# toplevel.net
KiCad netlist of a schematic drawn in Altium Designer
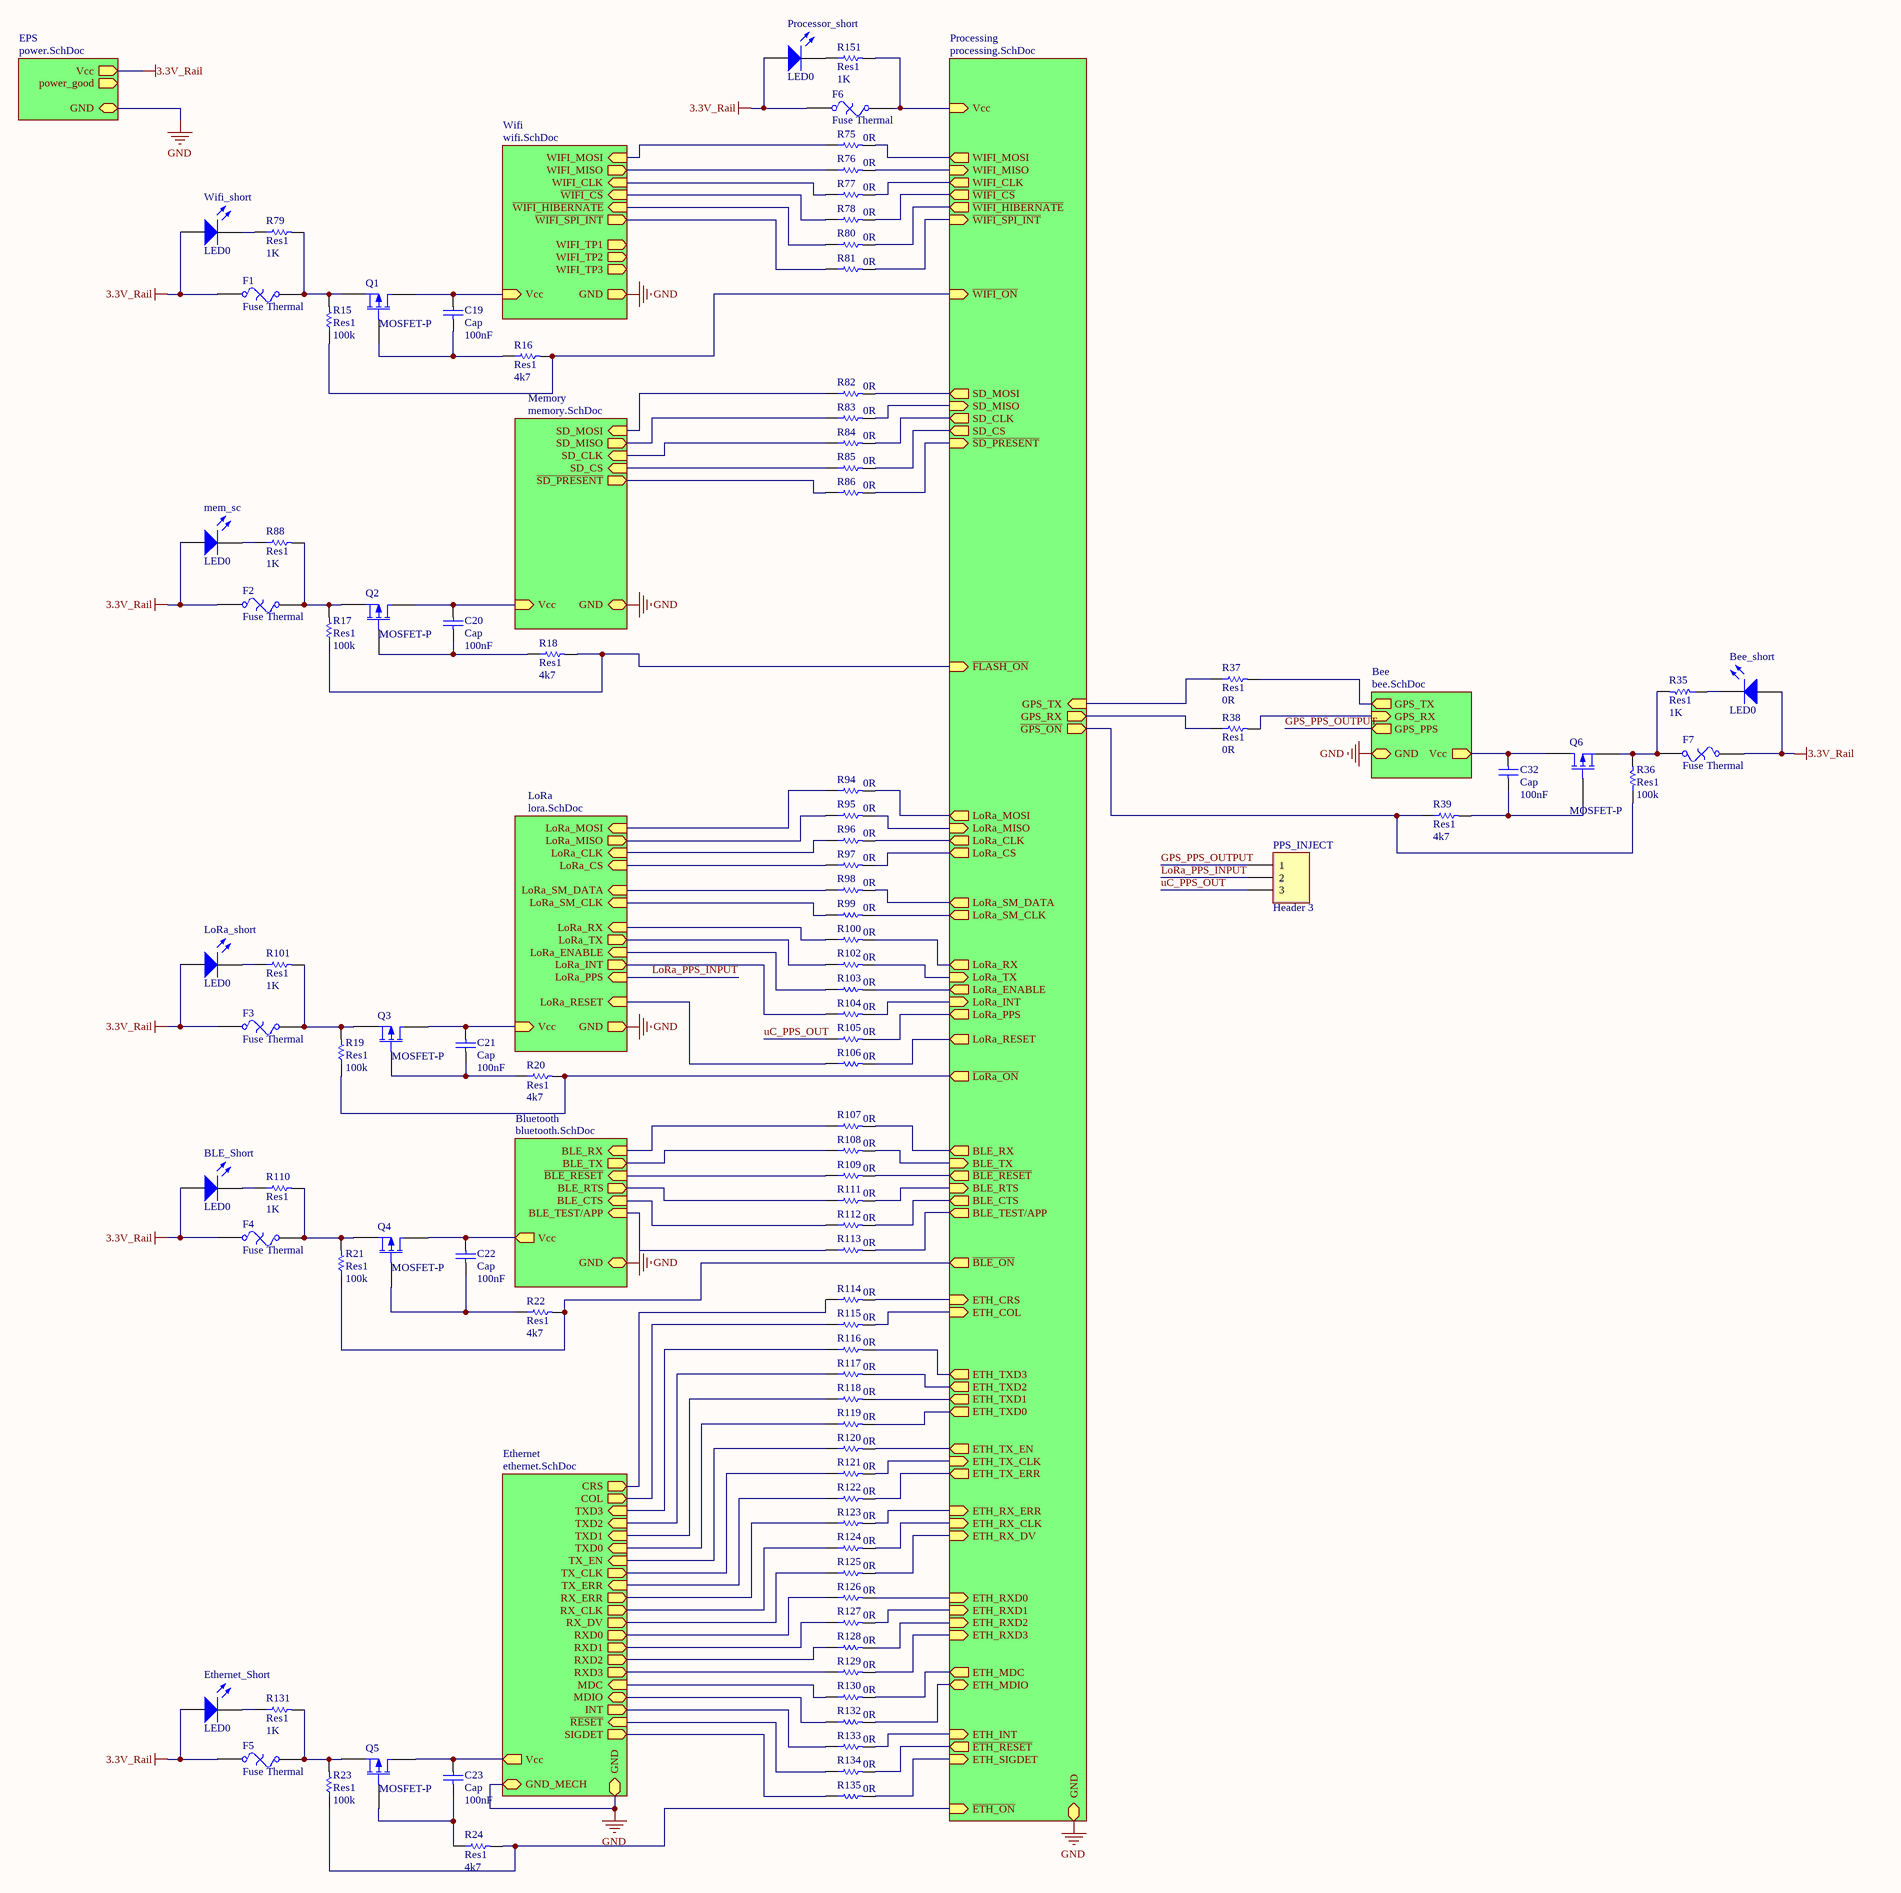
[diagram p0: toplevel.SchDoc]

(export (version "E")
  (design (tool "Eeschema 10.0.6"))
  (components
    (comp (ref "Bee_short")
      (value "LED0")
      (footprint "C0603")
      (description "Typical INFRARED GaAs LED")
      (fields (field (name "PUBLISHER") "Altium Limited"))
      (libsource (lib "any") (part "LED0"))
    )
    (comp (ref "BLE_Short")
      (value "LED0")
      (footprint "C0603")
      (description "Typical INFRARED GaAs LED")
      (fields (field (name "PUBLISHER") "Altium Limited"))
      (libsource (lib "any") (part "LED0"))
    )
    (comp (ref "C19")
      (value "Cap")
      (footprint "6-0805_L")
      (description "Capacitor")
      (fields (field (name "ALTIUM_VALUE") "100nF") (field (name "PUBLISHER") "Altium Limited"))
      (libsource (lib "Miscellaneous Devices") (part "Cap"))
    )
    (comp (ref "C20")
      (value "Cap")
      (footprint "6-0805_L")
      (description "Capacitor")
      (fields (field (name "ALTIUM_VALUE") "100nF") (field (name "PUBLISHER") "Altium Limited"))
      (libsource (lib "Miscellaneous Devices") (part "Cap"))
    )
    (comp (ref "C21")
      (value "Cap")
      (footprint "6-0805_L")
      (description "Capacitor")
      (fields (field (name "ALTIUM_VALUE") "100nF") (field (name "PUBLISHER") "Altium Limited"))
      (libsource (lib "Miscellaneous Devices") (part "Cap"))
    )
    (comp (ref "C22")
      (value "Cap")
      (footprint "6-0805_L")
      (description "Capacitor")
      (fields (field (name "ALTIUM_VALUE") "100nF") (field (name "PUBLISHER") "Altium Limited"))
      (libsource (lib "Miscellaneous Devices") (part "Cap"))
    )
    (comp (ref "C23")
      (value "Cap")
      (footprint "6-0805_L")
      (description "Capacitor")
      (fields (field (name "ALTIUM_VALUE") "100nF") (field (name "PUBLISHER") "Altium Limited"))
      (libsource (lib "Miscellaneous Devices") (part "Cap"))
    )
    (comp (ref "C32")
      (value "Cap")
      (footprint "6-0805_L")
      (description "Capacitor")
      (fields (field (name "ALTIUM_VALUE") "100nF") (field (name "PUBLISHER") "Altium Limited"))
      (libsource (lib "Miscellaneous Devices") (part "Cap"))
    )
    (comp (ref "Ethernet_Short")
      (value "LED0")
      (footprint "C0603")
      (description "Typical INFRARED GaAs LED")
      (fields (field (name "PUBLISHER") "Altium Limited"))
      (libsource (lib "any") (part "LED0"))
    )
    (comp (ref "F1")
      (value "Fuse Thermal")
      (footprint "1812-polyfuse")
      (description "Thermal Fuse")
      (fields (field (name "PUBLISHER") "Altium Limited"))
      (libsource (lib "Any") (part "Fuse Thermal"))
    )
    (comp (ref "F2")
      (value "Fuse Thermal")
      (footprint "1812-polyfuse")
      (description "Thermal Fuse")
      (fields (field (name "PUBLISHER") "Altium Limited"))
      (libsource (lib "Any") (part "Fuse Thermal"))
    )
    (comp (ref "F3")
      (value "Fuse Thermal")
      (footprint "1812-polyfuse")
      (description "Thermal Fuse")
      (fields (field (name "PUBLISHER") "Altium Limited"))
      (libsource (lib "Any") (part "Fuse Thermal"))
    )
    (comp (ref "F4")
      (value "Fuse Thermal")
      (footprint "1812-polyfuse")
      (description "Thermal Fuse")
      (fields (field (name "PUBLISHER") "Altium Limited"))
      (libsource (lib "Any") (part "Fuse Thermal"))
    )
    (comp (ref "F5")
      (value "Fuse Thermal")
      (footprint "1812-polyfuse")
      (description "Thermal Fuse")
      (fields (field (name "PUBLISHER") "Altium Limited"))
      (libsource (lib "Any") (part "Fuse Thermal"))
    )
    (comp (ref "F6")
      (value "Fuse Thermal")
      (footprint "1812-polyfuse")
      (description "Thermal Fuse")
      (fields (field (name "PUBLISHER") "Altium Limited"))
      (libsource (lib "Any") (part "Fuse Thermal"))
    )
    (comp (ref "F7")
      (value "Fuse Thermal")
      (footprint "1812-polyfuse")
      (description "Thermal Fuse")
      (fields (field (name "PUBLISHER") "Altium Limited"))
      (libsource (lib "") (part "Fuse Thermal_1"))
    )
    (comp (ref "LoRa_short")
      (value "LED0")
      (footprint "C0603")
      (description "Typical INFRARED GaAs LED")
      (fields (field (name "PUBLISHER") "Altium Limited"))
      (libsource (lib "any") (part "LED0"))
    )
    (comp (ref "mem_sc")
      (value "LED0")
      (footprint "C0603")
      (description "Typical INFRARED GaAs LED")
      (fields (field (name "PUBLISHER") "Altium Limited"))
      (libsource (lib "any") (part "LED0"))
    )
    (comp (ref "PPS_INJECT")
      (value "Header 3")
      (footprint "HDR1X3")
      (description "Header, 3-Pin")
      (fields (field (name "PUBLISHER") "Altium Limited"))
      (libsource (lib "Miscellaneous Connectors") (part "Header 3"))
    )
    (comp (ref "Processor_short")
      (value "LED0")
      (footprint "C0603")
      (description "Typical INFRARED GaAs LED")
      (fields (field (name "PUBLISHER") "Altium Limited"))
      (libsource (lib "any") (part "LED0"))
    )
    (comp (ref "Q1")
      (value "MOSFET-P")
      (footprint "SOT23_N")
      (description "P-Channel MOSFET")
      (fields (field (name "PUBLISHER") "Altium Limited"))
      (libsource (lib "Miscellaneous Devices") (part "MOSFET-P"))
    )
    (comp (ref "Q2")
      (value "MOSFET-P")
      (footprint "SOT23_N")
      (description "P-Channel MOSFET")
      (fields (field (name "PUBLISHER") "Altium Limited"))
      (libsource (lib "Miscellaneous Devices") (part "MOSFET-P"))
    )
    (comp (ref "Q3")
      (value "MOSFET-P")
      (footprint "SOT23_N")
      (description "P-Channel MOSFET")
      (fields (field (name "PUBLISHER") "Altium Limited"))
      (libsource (lib "Miscellaneous Devices") (part "MOSFET-P"))
    )
    (comp (ref "Q4")
      (value "MOSFET-P")
      (footprint "SOT23_N")
      (description "P-Channel MOSFET")
      (fields (field (name "PUBLISHER") "Altium Limited"))
      (libsource (lib "Miscellaneous Devices") (part "MOSFET-P"))
    )
    (comp (ref "Q5")
      (value "MOSFET-P")
      (footprint "SOT23_N")
      (description "P-Channel MOSFET")
      (fields (field (name "PUBLISHER") "Altium Limited"))
      (libsource (lib "Miscellaneous Devices") (part "MOSFET-P"))
    )
    (comp (ref "Q6")
      (value "MOSFET-P")
      (footprint "SOT23_N")
      (description "P-Channel MOSFET")
      (fields (field (name "PUBLISHER") "Altium Limited"))
      (libsource (lib "Miscellaneous Devices") (part "MOSFET-P"))
    )
    (comp (ref "R15")
      (value "Res1")
      (footprint "R0603")
      (description "Resistor")
      (fields (field (name "ALTIUM_VALUE") "100k") (field (name "PUBLISHER") "Altium Limited"))
      (libsource (lib "Miscellaneous Devices") (part "Res1"))
    )
    (comp (ref "R16")
      (value "Res1")
      (footprint "R0603")
      (description "Resistor")
      (fields (field (name "ALTIUM_VALUE") "4k7") (field (name "PUBLISHER") "Altium Limited"))
      (libsource (lib "Miscellaneous Devices") (part "Res1"))
    )
    (comp (ref "R17")
      (value "Res1")
      (footprint "R0603")
      (description "Resistor")
      (fields (field (name "ALTIUM_VALUE") "100k") (field (name "PUBLISHER") "Altium Limited"))
      (libsource (lib "Miscellaneous Devices") (part "Res1"))
    )
    (comp (ref "R18")
      (value "Res1")
      (footprint "R0603")
      (description "Resistor")
      (fields (field (name "ALTIUM_VALUE") "4k7") (field (name "PUBLISHER") "Altium Limited"))
      (libsource (lib "Miscellaneous Devices") (part "Res1"))
    )
    (comp (ref "R19")
      (value "Res1")
      (footprint "R0603")
      (description "Resistor")
      (fields (field (name "ALTIUM_VALUE") "100k") (field (name "PUBLISHER") "Altium Limited"))
      (libsource (lib "Miscellaneous Devices") (part "Res1"))
    )
    (comp (ref "R20")
      (value "Res1")
      (footprint "R0603")
      (description "Resistor")
      (fields (field (name "ALTIUM_VALUE") "4k7") (field (name "PUBLISHER") "Altium Limited"))
      (libsource (lib "Miscellaneous Devices") (part "Res1"))
    )
    (comp (ref "R21")
      (value "Res1")
      (footprint "R0603")
      (description "Resistor")
      (fields (field (name "ALTIUM_VALUE") "100k") (field (name "PUBLISHER") "Altium Limited"))
      (libsource (lib "Miscellaneous Devices") (part "Res1"))
    )
    (comp (ref "R22")
      (value "Res1")
      (footprint "R0603")
      (description "Resistor")
      (fields (field (name "ALTIUM_VALUE") "4k7") (field (name "PUBLISHER") "Altium Limited"))
      (libsource (lib "Miscellaneous Devices") (part "Res1"))
    )
    (comp (ref "R23")
      (value "Res1")
      (footprint "R0603")
      (description "Resistor")
      (fields (field (name "ALTIUM_VALUE") "100k") (field (name "PUBLISHER") "Altium Limited"))
      (libsource (lib "Miscellaneous Devices") (part "Res1"))
    )
    (comp (ref "R24")
      (value "Res1")
      (footprint "R0603")
      (description "Resistor")
      (fields (field (name "ALTIUM_VALUE") "4k7") (field (name "PUBLISHER") "Altium Limited"))
      (libsource (lib "Miscellaneous Devices") (part "Res1"))
    )
    (comp (ref "R35")
      (value "Res1")
      (footprint "R0603")
      (description "Resistor")
      (fields (field (name "ALTIUM_VALUE") "1K") (field (name "PUBLISHER") "Altium Limited"))
      (libsource (lib "any") (part "Res1"))
    )
    (comp (ref "R36")
      (value "Res1")
      (footprint "R0603")
      (description "Resistor")
      (fields (field (name "ALTIUM_VALUE") "100k") (field (name "PUBLISHER") "Altium Limited"))
      (libsource (lib "Miscellaneous Devices") (part "Res1"))
    )
    (comp (ref "R37")
      (value "Res1")
      (footprint "R0603")
      (description "Resistor")
      (fields (field (name "ALTIUM_VALUE") "0R") (field (name "PUBLISHER") "Altium Limited"))
      (libsource (lib "Miscellaneous Devices") (part "Res1"))
    )
    (comp (ref "R38")
      (value "Res1")
      (footprint "R0603")
      (description "Resistor")
      (fields (field (name "ALTIUM_VALUE") "0R") (field (name "PUBLISHER") "Altium Limited"))
      (libsource (lib "Miscellaneous Devices") (part "Res1"))
    )
    (comp (ref "R39")
      (value "Res1")
      (footprint "R0603")
      (description "Resistor")
      (fields (field (name "ALTIUM_VALUE") "4k7") (field (name "PUBLISHER") "Altium Limited"))
      (libsource (lib "Miscellaneous Devices") (part "Res1"))
    )
    (comp (ref "R75")
      (value "0R")
      (footprint "R0603")
      (description "Resistor")
      (fields (field (name "PUBLISHER") "Altium Limited"))
      (libsource (lib "any") (part "Res1"))
    )
    (comp (ref "R76")
      (value "0R")
      (footprint "R0603")
      (description "Resistor")
      (fields (field (name "PUBLISHER") "Altium Limited"))
      (libsource (lib "any") (part "Res1"))
    )
    (comp (ref "R77")
      (value "0R")
      (footprint "R0603")
      (description "Resistor")
      (fields (field (name "PUBLISHER") "Altium Limited"))
      (libsource (lib "any") (part "Res1"))
    )
    (comp (ref "R78")
      (value "0R")
      (footprint "R0603")
      (description "Resistor")
      (fields (field (name "PUBLISHER") "Altium Limited"))
      (libsource (lib "any") (part "Res1"))
    )
    (comp (ref "R79")
      (value "Res1")
      (footprint "R0603")
      (description "Resistor")
      (fields (field (name "ALTIUM_VALUE") "1K") (field (name "PUBLISHER") "Altium Limited"))
      (libsource (lib "any") (part "Res1"))
    )
    (comp (ref "R80")
      (value "0R")
      (footprint "R0603")
      (description "Resistor")
      (fields (field (name "PUBLISHER") "Altium Limited"))
      (libsource (lib "any") (part "Res1"))
    )
    (comp (ref "R81")
      (value "0R")
      (footprint "R0603")
      (description "Resistor")
      (fields (field (name "PUBLISHER") "Altium Limited"))
      (libsource (lib "any") (part "Res1"))
    )
    (comp (ref "R82")
      (value "0R")
      (footprint "R0603")
      (description "Resistor")
      (fields (field (name "PUBLISHER") "Altium Limited"))
      (libsource (lib "any") (part "Res1"))
    )
    (comp (ref "R83")
      (value "0R")
      (footprint "R0603")
      (description "Resistor")
      (fields (field (name "PUBLISHER") "Altium Limited"))
      (libsource (lib "any") (part "Res1"))
    )
    (comp (ref "R84")
      (value "0R")
      (footprint "R0603")
      (description "Resistor")
      (fields (field (name "PUBLISHER") "Altium Limited"))
      (libsource (lib "any") (part "Res1"))
    )
    (comp (ref "R85")
      (value "0R")
      (footprint "R0603")
      (description "Resistor")
      (fields (field (name "PUBLISHER") "Altium Limited"))
      (libsource (lib "any") (part "Res1"))
    )
    (comp (ref "R86")
      (value "0R")
      (footprint "R0603")
      (description "Resistor")
      (fields (field (name "PUBLISHER") "Altium Limited"))
      (libsource (lib "any") (part "Res1"))
    )
    (comp (ref "R88")
      (value "Res1")
      (footprint "R0603")
      (description "Resistor")
      (fields (field (name "ALTIUM_VALUE") "1K") (field (name "PUBLISHER") "Altium Limited"))
      (libsource (lib "any") (part "Res1"))
    )
    (comp (ref "R94")
      (value "0R")
      (footprint "R0603")
      (description "Resistor")
      (fields (field (name "PUBLISHER") "Altium Limited"))
      (libsource (lib "any") (part "Res1"))
    )
    (comp (ref "R95")
      (value "0R")
      (footprint "R0603")
      (description "Resistor")
      (fields (field (name "PUBLISHER") "Altium Limited"))
      (libsource (lib "any") (part "Res1"))
    )
    (comp (ref "R96")
      (value "0R")
      (footprint "R0603")
      (description "Resistor")
      (fields (field (name "PUBLISHER") "Altium Limited"))
      (libsource (lib "any") (part "Res1"))
    )
    (comp (ref "R97")
      (value "0R")
      (footprint "R0603")
      (description "Resistor")
      (fields (field (name "PUBLISHER") "Altium Limited"))
      (libsource (lib "any") (part "Res1"))
    )
    (comp (ref "R98")
      (value "0R")
      (footprint "R0603")
      (description "Resistor")
      (fields (field (name "PUBLISHER") "Altium Limited"))
      (libsource (lib "any") (part "Res1"))
    )
    (comp (ref "R99")
      (value "0R")
      (footprint "R0603")
      (description "Resistor")
      (fields (field (name "PUBLISHER") "Altium Limited"))
      (libsource (lib "any") (part "Res1"))
    )
    (comp (ref "R100")
      (value "0R")
      (footprint "R0603")
      (description "Resistor")
      (fields (field (name "PUBLISHER") "Altium Limited"))
      (libsource (lib "any") (part "Res1"))
    )
    (comp (ref "R101")
      (value "Res1")
      (footprint "R0603")
      (description "Resistor")
      (fields (field (name "ALTIUM_VALUE") "1K") (field (name "PUBLISHER") "Altium Limited"))
      (libsource (lib "any") (part "Res1"))
    )
    (comp (ref "R102")
      (value "0R")
      (footprint "R0603")
      (description "Resistor")
      (fields (field (name "PUBLISHER") "Altium Limited"))
      (libsource (lib "any") (part "Res1"))
    )
    (comp (ref "R103")
      (value "0R")
      (footprint "R0603")
      (description "Resistor")
      (fields (field (name "PUBLISHER") "Altium Limited"))
      (libsource (lib "any") (part "Res1"))
    )
    (comp (ref "R104")
      (value "0R")
      (footprint "R0603")
      (description "Resistor")
      (fields (field (name "PUBLISHER") "Altium Limited"))
      (libsource (lib "any") (part "Res1"))
    )
    (comp (ref "R105")
      (value "0R")
      (footprint "R0603")
      (description "Resistor")
      (fields (field (name "PUBLISHER") "Altium Limited"))
      (libsource (lib "any") (part "Res1"))
    )
    (comp (ref "R106")
      (value "0R")
      (footprint "R0603")
      (description "Resistor")
      (fields (field (name "PUBLISHER") "Altium Limited"))
      (libsource (lib "any") (part "Res1"))
    )
    (comp (ref "R107")
      (value "0R")
      (footprint "R0603")
      (description "Resistor")
      (fields (field (name "PUBLISHER") "Altium Limited"))
      (libsource (lib "any") (part "Res1"))
    )
    (comp (ref "R108")
      (value "0R")
      (footprint "R0603")
      (description "Resistor")
      (fields (field (name "PUBLISHER") "Altium Limited"))
      (libsource (lib "any") (part "Res1"))
    )
    (comp (ref "R109")
      (value "0R")
      (footprint "R0603")
      (description "Resistor")
      (fields (field (name "PUBLISHER") "Altium Limited"))
      (libsource (lib "any") (part "Res1"))
    )
    (comp (ref "R110")
      (value "Res1")
      (footprint "R0603")
      (description "Resistor")
      (fields (field (name "ALTIUM_VALUE") "1K") (field (name "PUBLISHER") "Altium Limited"))
      (libsource (lib "any") (part "Res1"))
    )
    (comp (ref "R111")
      (value "0R")
      (footprint "R0603")
      (description "Resistor")
      (fields (field (name "PUBLISHER") "Altium Limited"))
      (libsource (lib "any") (part "Res1"))
    )
    (comp (ref "R112")
      (value "0R")
      (footprint "R0603")
      (description "Resistor")
      (fields (field (name "PUBLISHER") "Altium Limited"))
      (libsource (lib "any") (part "Res1"))
    )
    (comp (ref "R113")
      (value "0R")
      (footprint "R0603")
      (description "Resistor")
      (fields (field (name "PUBLISHER") "Altium Limited"))
      (libsource (lib "any") (part "Res1"))
    )
    (comp (ref "R114")
      (value "0R")
      (footprint "R0603")
      (description "Resistor")
      (fields (field (name "PUBLISHER") "Altium Limited"))
      (libsource (lib "any") (part "Res1"))
    )
    (comp (ref "R115")
      (value "0R")
      (footprint "R0603")
      (description "Resistor")
      (fields (field (name "PUBLISHER") "Altium Limited"))
      (libsource (lib "any") (part "Res1"))
    )
    (comp (ref "R116")
      (value "0R")
      (footprint "R0603")
      (description "Resistor")
      (fields (field (name "PUBLISHER") "Altium Limited"))
      (libsource (lib "any") (part "Res1"))
    )
    (comp (ref "R117")
      (value "0R")
      (footprint "R0603")
      (description "Resistor")
      (fields (field (name "PUBLISHER") "Altium Limited"))
      (libsource (lib "any") (part "Res1"))
    )
    (comp (ref "R118")
      (value "0R")
      (footprint "R0603")
      (description "Resistor")
      (fields (field (name "PUBLISHER") "Altium Limited"))
      (libsource (lib "any") (part "Res1"))
    )
    (comp (ref "R119")
      (value "0R")
      (footprint "R0603")
      (description "Resistor")
      (fields (field (name "PUBLISHER") "Altium Limited"))
      (libsource (lib "any") (part "Res1"))
    )
    (comp (ref "R120")
      (value "0R")
      (footprint "R0603")
      (description "Resistor")
      (fields (field (name "PUBLISHER") "Altium Limited"))
      (libsource (lib "any") (part "Res1"))
    )
    (comp (ref "R121")
      (value "0R")
      (footprint "R0603")
      (description "Resistor")
      (fields (field (name "PUBLISHER") "Altium Limited"))
      (libsource (lib "any") (part "Res1"))
    )
    (comp (ref "R122")
      (value "0R")
      (footprint "R0603")
      (description "Resistor")
      (fields (field (name "PUBLISHER") "Altium Limited"))
      (libsource (lib "any") (part "Res1"))
    )
    (comp (ref "R123")
      (value "0R")
      (footprint "R0603")
      (description "Resistor")
      (fields (field (name "PUBLISHER") "Altium Limited"))
      (libsource (lib "any") (part "Res1"))
    )
    (comp (ref "R124")
      (value "0R")
      (footprint "R0603")
      (description "Resistor")
      (fields (field (name "PUBLISHER") "Altium Limited"))
      (libsource (lib "any") (part "Res1"))
    )
    (comp (ref "R125")
      (value "0R")
      (footprint "R0603")
      (description "Resistor")
      (fields (field (name "PUBLISHER") "Altium Limited"))
      (libsource (lib "any") (part "Res1"))
    )
    (comp (ref "R126")
      (value "0R")
      (footprint "R0603")
      (description "Resistor")
      (fields (field (name "PUBLISHER") "Altium Limited"))
      (libsource (lib "any") (part "Res1"))
    )
    (comp (ref "R127")
      (value "0R")
      (footprint "R0603")
      (description "Resistor")
      (fields (field (name "PUBLISHER") "Altium Limited"))
      (libsource (lib "any") (part "Res1"))
    )
    (comp (ref "R128")
      (value "0R")
      (footprint "R0603")
      (description "Resistor")
      (fields (field (name "PUBLISHER") "Altium Limited"))
      (libsource (lib "any") (part "Res1"))
    )
    (comp (ref "R129")
      (value "0R")
      (footprint "R0603")
      (description "Resistor")
      (fields (field (name "PUBLISHER") "Altium Limited"))
      (libsource (lib "any") (part "Res1"))
    )
    (comp (ref "R130")
      (value "0R")
      (footprint "R0603")
      (description "Resistor")
      (fields (field (name "PUBLISHER") "Altium Limited"))
      (libsource (lib "any") (part "Res1"))
    )
    (comp (ref "R131")
      (value "Res1")
      (footprint "R0603")
      (description "Resistor")
      (fields (field (name "ALTIUM_VALUE") "1K") (field (name "PUBLISHER") "Altium Limited"))
      (libsource (lib "any") (part "Res1"))
    )
    (comp (ref "R132")
      (value "0R")
      (footprint "R0603")
      (description "Resistor")
      (fields (field (name "PUBLISHER") "Altium Limited"))
      (libsource (lib "any") (part "Res1"))
    )
    (comp (ref "R133")
      (value "0R")
      (footprint "R0603")
      (description "Resistor")
      (fields (field (name "PUBLISHER") "Altium Limited"))
      (libsource (lib "any") (part "Res1"))
    )
    (comp (ref "R134")
      (value "0R")
      (footprint "R0603")
      (description "Resistor")
      (fields (field (name "PUBLISHER") "Altium Limited"))
      (libsource (lib "any") (part "Res1"))
    )
    (comp (ref "R135")
      (value "0R")
      (footprint "R0603")
      (description "Resistor")
      (fields (field (name "PUBLISHER") "Altium Limited"))
      (libsource (lib "any") (part "Res1"))
    )
    (comp (ref "R151")
      (value "Res1")
      (footprint "R0603")
      (description "Resistor")
      (fields (field (name "ALTIUM_VALUE") "1K") (field (name "PUBLISHER") "Altium Limited"))
      (libsource (lib "any") (part "Res1"))
    )
    (comp (ref "Wifi_short")
      (value "LED0")
      (footprint "C0603")
      (description "Typical INFRARED GaAs LED")
      (fields (field (name "PUBLISHER") "Altium Limited"))
      (libsource (lib "any") (part "LED0"))
    )
  )
  (nets
    (net (code "1") (name "/BLE_CTS") (class "Default")
      (node (ref "R112") (pin "1") (pinfunction "1_1") (pintype "passive"))
    )
    (net (code "2") (name "/BLE_CTS_1") (class "Default")
      (node (ref "R112") (pin "2") (pinfunction "2_2") (pintype "passive"))
    )
    (net (code "3") (name "/BLE_RTS") (class "Default")
      (node (ref "R111") (pin "1") (pinfunction "1_1") (pintype "passive"))
    )
    (net (code "4") (name "/BLE_RTS_1") (class "Default")
      (node (ref "R111") (pin "2") (pinfunction "2_2") (pintype "passive"))
    )
    (net (code "5") (name "/BLE_RX") (class "Default")
      (node (ref "R107") (pin "1") (pinfunction "1_1") (pintype "passive"))
    )
    (net (code "6") (name "/BLE_RX_1") (class "Default")
      (node (ref "R107") (pin "2") (pinfunction "2_2") (pintype "passive"))
    )
    (net (code "7") (name "/BLE_TEST{slash}APP") (class "Default")
      (node (ref "R113") (pin "2") (pinfunction "2_2") (pintype "passive"))
    )
    (net (code "8") (name "/BLE_TEST{slash}APP_1") (class "Default")
      (node (ref "R113") (pin "1") (pinfunction "1_1") (pintype "passive"))
    )
    (net (code "9") (name "/BLE_TX") (class "Default")
      (node (ref "R108") (pin "1") (pinfunction "1_1") (pintype "passive"))
    )
    (net (code "10") (name "/BLE_TX_1") (class "Default")
      (node (ref "R108") (pin "2") (pinfunction "2_2") (pintype "passive"))
    )
    (net (code "11") (name "/COL") (class "Default")
      (node (ref "R115") (pin "1") (pinfunction "1_1") (pintype "passive"))
    )
    (net (code "12") (name "/CRS") (class "Default")
      (node (ref "R114") (pin "1") (pinfunction "1_1") (pintype "passive"))
    )
    (net (code "13") (name "/ETH_COL") (class "Default")
      (node (ref "R115") (pin "2") (pinfunction "2_2") (pintype "passive"))
    )
    (net (code "14") (name "/ETH_CRS") (class "Default")
      (node (ref "R114") (pin "2") (pinfunction "2_2") (pintype "passive"))
    )
    (net (code "15") (name "/ETH_INT") (class "Default")
      (node (ref "R133") (pin "2") (pinfunction "2_2") (pintype "passive"))
    )
    (net (code "16") (name "/ETH_MDC") (class "Default")
      (node (ref "R130") (pin "2") (pinfunction "2_2") (pintype "passive"))
    )
    (net (code "17") (name "/ETH_MDIO") (class "Default")
      (node (ref "R132") (pin "2") (pinfunction "2_2") (pintype "passive"))
    )
    (net (code "18") (name "/ETH_RXD0") (class "Default")
      (node (ref "R126") (pin "2") (pinfunction "2_2") (pintype "passive"))
    )
    (net (code "19") (name "/ETH_RXD1") (class "Default")
      (node (ref "R127") (pin "2") (pinfunction "2_2") (pintype "passive"))
    )
    (net (code "20") (name "/ETH_RXD2") (class "Default")
      (node (ref "R128") (pin "2") (pinfunction "2_2") (pintype "passive"))
    )
    (net (code "21") (name "/ETH_RXD3") (class "Default")
      (node (ref "R129") (pin "2") (pinfunction "2_2") (pintype "passive"))
    )
    (net (code "22") (name "/ETH_RX_CLK") (class "Default")
      (node (ref "R124") (pin "2") (pinfunction "2_2") (pintype "passive"))
    )
    (net (code "23") (name "/ETH_RX_DV") (class "Default")
      (node (ref "R125") (pin "2") (pinfunction "2_2") (pintype "passive"))
    )
    (net (code "24") (name "/ETH_RX_ERR") (class "Default")
      (node (ref "R123") (pin "2") (pinfunction "2_2") (pintype "passive"))
    )
    (net (code "25") (name "/ETH_SIGDET") (class "Default")
      (node (ref "R135") (pin "2") (pinfunction "2_2") (pintype "passive"))
    )
    (net (code "26") (name "/ETH_TXD0") (class "Default")
      (node (ref "R119") (pin "2") (pinfunction "2_2") (pintype "passive"))
    )
    (net (code "27") (name "/ETH_TXD1") (class "Default")
      (node (ref "R118") (pin "2") (pinfunction "2_2") (pintype "passive"))
    )
    (net (code "28") (name "/ETH_TXD2") (class "Default")
      (node (ref "R117") (pin "2") (pinfunction "2_2") (pintype "passive"))
    )
    (net (code "29") (name "/ETH_TXD3") (class "Default")
      (node (ref "R116") (pin "2") (pinfunction "2_2") (pintype "passive"))
    )
    (net (code "30") (name "/ETH_TX_CLK") (class "Default")
      (node (ref "R121") (pin "2") (pinfunction "2_2") (pintype "passive"))
    )
    (net (code "31") (name "/ETH_TX_EN") (class "Default")
      (node (ref "R120") (pin "2") (pinfunction "2_2") (pintype "passive"))
    )
    (net (code "32") (name "/ETH_TX_ERR") (class "Default")
      (node (ref "R122") (pin "2") (pinfunction "2_2") (pintype "passive"))
    )
    (net (code "33") (name "/GPS_PPS_OUTPUT") (class "Default")
      (node (ref "PPS_INJECT") (pin "1") (pinfunction "1_1") (pintype "passive"))
    )
    (net (code "34") (name "/GPS_RX") (class "Default")
      (node (ref "R38") (pin "1") (pinfunction "1_1") (pintype "passive"))
    )
    (net (code "35") (name "/GPS_RX_1") (class "Default")
      (node (ref "R38") (pin "2") (pinfunction "2_2") (pintype "passive"))
    )
    (net (code "36") (name "/GPS_TX") (class "Default")
      (node (ref "R37") (pin "1") (pinfunction "1_1") (pintype "passive"))
    )
    (net (code "37") (name "/GPS_TX_1") (class "Default")
      (node (ref "R37") (pin "2") (pinfunction "2_2") (pintype "passive"))
    )
    (net (code "38") (name "/INT") (class "Default")
      (node (ref "R133") (pin "1") (pinfunction "1_1") (pintype "passive"))
    )
    (net (code "39") (name "/LoRa_CLK") (class "Default")
      (node (ref "R96") (pin "2") (pinfunction "2_2") (pintype "passive"))
    )
    (net (code "40") (name "/LoRa_CLK_1") (class "Default")
      (node (ref "R96") (pin "1") (pinfunction "1_1") (pintype "passive"))
    )
    (net (code "41") (name "/LoRa_CS") (class "Default")
      (node (ref "R97") (pin "2") (pinfunction "2_2") (pintype "passive"))
    )
    (net (code "42") (name "/LoRa_CS_1") (class "Default")
      (node (ref "R97") (pin "1") (pinfunction "1_1") (pintype "passive"))
    )
    (net (code "43") (name "/LoRa_ENABLE") (class "Default")
      (node (ref "R103") (pin "2") (pinfunction "2_2") (pintype "passive"))
    )
    (net (code "44") (name "/LoRa_ENABLE_1") (class "Default")
      (node (ref "R103") (pin "1") (pinfunction "1_1") (pintype "passive"))
    )
    (net (code "45") (name "/LoRa_INT") (class "Default")
      (node (ref "R104") (pin "2") (pinfunction "2_2") (pintype "passive"))
    )
    (net (code "46") (name "/LoRa_INT_1") (class "Default")
      (node (ref "R104") (pin "1") (pinfunction "1_1") (pintype "passive"))
    )
    (net (code "47") (name "/LoRa_MISO") (class "Default")
      (node (ref "R95") (pin "2") (pinfunction "2_2") (pintype "passive"))
    )
    (net (code "48") (name "/LoRa_MISO_1") (class "Default")
      (node (ref "R95") (pin "1") (pinfunction "1_1") (pintype "passive"))
    )
    (net (code "49") (name "/LoRa_MOSI") (class "Default")
      (node (ref "R94") (pin "2") (pinfunction "2_2") (pintype "passive"))
    )
    (net (code "50") (name "/LoRa_MOSI_1") (class "Default")
      (node (ref "R94") (pin "1") (pinfunction "1_1") (pintype "passive"))
    )
    (net (code "51") (name "/LoRa_PPS") (class "Default")
      (node (ref "R105") (pin "2") (pinfunction "2_2") (pintype "passive"))
    )
    (net (code "52") (name "/LoRa_PPS_INPUT") (class "Default")
      (node (ref "PPS_INJECT") (pin "2") (pinfunction "2_2") (pintype "passive"))
    )
    (net (code "53") (name "/LoRa_RESET") (class "Default")
      (node (ref "R106") (pin "2") (pinfunction "2_2") (pintype "passive"))
    )
    (net (code "54") (name "/LoRa_RESET_1") (class "Default")
      (node (ref "R106") (pin "1") (pinfunction "1_1") (pintype "passive"))
    )
    (net (code "55") (name "/LoRa_RX") (class "Default")
      (node (ref "R100") (pin "2") (pinfunction "2_2") (pintype "passive"))
    )
    (net (code "56") (name "/LoRa_RX_1") (class "Default")
      (node (ref "R100") (pin "1") (pinfunction "1_1") (pintype "passive"))
    )
    (net (code "57") (name "/LoRa_SM_CLK") (class "Default")
      (node (ref "R99") (pin "2") (pinfunction "2_2") (pintype "passive"))
    )
    (net (code "58") (name "/LoRa_SM_CLK_1") (class "Default")
      (node (ref "R99") (pin "1") (pinfunction "1_1") (pintype "passive"))
    )
    (net (code "59") (name "/LoRa_SM_DATA") (class "Default")
      (node (ref "R98") (pin "2") (pinfunction "2_2") (pintype "passive"))
    )
    (net (code "60") (name "/LoRa_SM_DATA_1") (class "Default")
      (node (ref "R98") (pin "1") (pinfunction "1_1") (pintype "passive"))
    )
    (net (code "61") (name "/LoRa_TX") (class "Default")
      (node (ref "R102") (pin "2") (pinfunction "2_2") (pintype "passive"))
    )
    (net (code "62") (name "/LoRa_TX_1") (class "Default")
      (node (ref "R102") (pin "1") (pinfunction "1_1") (pintype "passive"))
    )
    (net (code "63") (name "/MDC") (class "Default")
      (node (ref "R130") (pin "1") (pinfunction "1_1") (pintype "passive"))
    )
    (net (code "64") (name "/MDIO") (class "Default")
      (node (ref "R132") (pin "1") (pinfunction "1_1") (pintype "passive"))
    )
    (net (code "65") (name "/RXD0") (class "Default")
      (node (ref "R126") (pin "1") (pinfunction "1_1") (pintype "passive"))
    )
    (net (code "66") (name "/RXD1") (class "Default")
      (node (ref "R127") (pin "1") (pinfunction "1_1") (pintype "passive"))
    )
    (net (code "67") (name "/RXD2") (class "Default")
      (node (ref "R128") (pin "1") (pinfunction "1_1") (pintype "passive"))
    )
    (net (code "68") (name "/RXD3") (class "Default")
      (node (ref "R129") (pin "1") (pinfunction "1_1") (pintype "passive"))
    )
    (net (code "69") (name "/RX_CLK") (class "Default")
      (node (ref "R124") (pin "1") (pinfunction "1_1") (pintype "passive"))
    )
    (net (code "70") (name "/RX_DV") (class "Default")
      (node (ref "R125") (pin "1") (pinfunction "1_1") (pintype "passive"))
    )
    (net (code "71") (name "/RX_ERR") (class "Default")
      (node (ref "R123") (pin "1") (pinfunction "1_1") (pintype "passive"))
    )
    (net (code "72") (name "/SD_CLK") (class "Default")
      (node (ref "R84") (pin "2") (pinfunction "2_2") (pintype "passive"))
    )
    (net (code "73") (name "/SD_CLK_1") (class "Default")
      (node (ref "R84") (pin "1") (pinfunction "1_1") (pintype "passive"))
    )
    (net (code "74") (name "/SD_CS") (class "Default")
      (node (ref "R85") (pin "1") (pinfunction "1_1") (pintype "passive"))
    )
    (net (code "75") (name "/SD_CS_1") (class "Default")
      (node (ref "R85") (pin "2") (pinfunction "2_2") (pintype "passive"))
    )
    (net (code "76") (name "/SD_MISO") (class "Default")
      (node (ref "R83") (pin "2") (pinfunction "2_2") (pintype "passive"))
    )
    (net (code "77") (name "/SD_MISO_1") (class "Default")
      (node (ref "R83") (pin "1") (pinfunction "1_1") (pintype "passive"))
    )
    (net (code "78") (name "/SD_MOSI") (class "Default")
      (node (ref "R82") (pin "2") (pinfunction "2_2") (pintype "passive"))
    )
    (net (code "79") (name "/SD_MOSI_1") (class "Default")
      (node (ref "R82") (pin "1") (pinfunction "1_1") (pintype "passive"))
    )
    (net (code "80") (name "/SIGDET") (class "Default")
      (node (ref "R135") (pin "1") (pinfunction "1_1") (pintype "passive"))
    )
    (net (code "81") (name "/TXD0") (class "Default")
      (node (ref "R119") (pin "1") (pinfunction "1_1") (pintype "passive"))
    )
    (net (code "82") (name "/TXD1") (class "Default")
      (node (ref "R118") (pin "1") (pinfunction "1_1") (pintype "passive"))
    )
    (net (code "83") (name "/TXD2") (class "Default")
      (node (ref "R117") (pin "1") (pinfunction "1_1") (pintype "passive"))
    )
    (net (code "84") (name "/TXD3") (class "Default")
      (node (ref "R116") (pin "1") (pinfunction "1_1") (pintype "passive"))
    )
    (net (code "85") (name "/TX_CLK") (class "Default")
      (node (ref "R121") (pin "1") (pinfunction "1_1") (pintype "passive"))
    )
    (net (code "86") (name "/TX_EN") (class "Default")
      (node (ref "R120") (pin "1") (pinfunction "1_1") (pintype "passive"))
    )
    (net (code "87") (name "/TX_ERR") (class "Default")
      (node (ref "R122") (pin "1") (pinfunction "1_1") (pintype "passive"))
    )
    (net (code "88") (name "/Vcc") (class "Default")
      (node (ref "C23") (pin "2") (pinfunction "2_2") (pintype "passive"))
      (node (ref "Q5") (pin "1") (pinfunction "D_1") (pintype "passive"))
    )
    (net (code "89") (name "/Vcc_1") (class "Default")
      (node (ref "C32") (pin "2") (pinfunction "2_2") (pintype "passive"))
      (node (ref "Q6") (pin "1") (pinfunction "D_1") (pintype "passive"))
    )
    (net (code "90") (name "/Vcc_2") (class "Default")
      (node (ref "C21") (pin "2") (pinfunction "2_2") (pintype "passive"))
      (node (ref "Q3") (pin "1") (pinfunction "D_1") (pintype "passive"))
    )
    (net (code "91") (name "/Vcc_3") (class "Default")
      (node (ref "C19") (pin "2") (pinfunction "2_2") (pintype "passive"))
      (node (ref "Q1") (pin "1") (pinfunction "D_1") (pintype "passive"))
    )
    (net (code "92") (name "/Vcc_4") (class "Default")
      (node (ref "C20") (pin "2") (pinfunction "2_2") (pintype "passive"))
      (node (ref "Q2") (pin "1") (pinfunction "D_1") (pintype "passive"))
    )
    (net (code "93") (name "/Vcc_5") (class "Default")
      (node (ref "C22") (pin "2") (pinfunction "2_2") (pintype "passive"))
      (node (ref "Q4") (pin "1") (pinfunction "D_1") (pintype "passive"))
    )
    (net (code "94") (name "/Vcc_6") (class "Default")
      (node (ref "F6") (pin "2") (pinfunction "2_2") (pintype "passive"))
      (node (ref "R151") (pin "2") (pinfunction "2_2") (pintype "passive"))
    )
    (net (code "95") (name "/WIFI_CLK") (class "Default")
      (node (ref "R77") (pin "2") (pinfunction "2_2") (pintype "passive"))
    )
    (net (code "96") (name "/WIFI_CLK_1") (class "Default")
      (node (ref "R77") (pin "1") (pinfunction "1_1") (pintype "passive"))
    )
    (net (code "97") (name "/WIFI_MISO") (class "Default")
      (node (ref "R76") (pin "2") (pinfunction "2_2") (pintype "passive"))
    )
    (net (code "98") (name "/WIFI_MISO_1") (class "Default")
      (node (ref "R76") (pin "1") (pinfunction "1_1") (pintype "passive"))
    )
    (net (code "99") (name "/WIFI_MOSI") (class "Default")
      (node (ref "R75") (pin "2") (pinfunction "2_2") (pintype "passive"))
    )
    (net (code "100") (name "/WIFI_MOSI_1") (class "Default")
      (node (ref "R75") (pin "1") (pinfunction "1_1") (pintype "passive"))
    )
    (net (code "105") (name "/uC_PPS_OUT") (class "Default")
      (node (ref "PPS_INJECT") (pin "3") (pinfunction "3_3") (pintype "passive"))
      (node (ref "R105") (pin "1") (pinfunction "1_1") (pintype "passive"))
    )
    (net (code "106") (name "/~{BLE_ON}") (class "Default")
      (node (ref "R21") (pin "1") (pinfunction "1_1") (pintype "passive"))
      (node (ref "R22") (pin "2") (pinfunction "2_2") (pintype "passive"))
    )
    (net (code "107") (name "/~{BLE_RESET}") (class "Default")
      (node (ref "R109") (pin "1") (pinfunction "1_1") (pintype "passive"))
    )
    (net (code "108") (name "/~{BLE_RESET}_1") (class "Default")
      (node (ref "R109") (pin "2") (pinfunction "2_2") (pintype "passive"))
    )
    (net (code "109") (name "/~{ETH_ON}") (class "Default")
      (node (ref "R23") (pin "1") (pinfunction "1_1") (pintype "passive"))
      (node (ref "R24") (pin "2") (pinfunction "2_2") (pintype "passive"))
    )
    (net (code "110") (name "/~{ETH_RESET}") (class "Default")
      (node (ref "R134") (pin "2") (pinfunction "2_2") (pintype "passive"))
    )
    (net (code "111") (name "/~{FLASH_ON}") (class "Default")
      (node (ref "R17") (pin "1") (pinfunction "1_1") (pintype "passive"))
      (node (ref "R18") (pin "2") (pinfunction "2_2") (pintype "passive"))
    )
    (net (code "112") (name "/~{GPS_ON}") (class "Default")
      (node (ref "R36") (pin "1") (pinfunction "1_1") (pintype "passive"))
      (node (ref "R39") (pin "1") (pinfunction "1_1") (pintype "passive"))
    )
    (net (code "113") (name "/~{LoRa_ON}") (class "Default")
      (node (ref "R19") (pin "1") (pinfunction "1_1") (pintype "passive"))
      (node (ref "R20") (pin "2") (pinfunction "2_2") (pintype "passive"))
    )
    (net (code "114") (name "/~{RESET}") (class "Default")
      (node (ref "R134") (pin "1") (pinfunction "1_1") (pintype "passive"))
    )
    (net (code "115") (name "/~{SD_PRESENT}") (class "Default")
      (node (ref "R86") (pin "1") (pinfunction "1_1") (pintype "passive"))
    )
    (net (code "116") (name "/~{SD_PRESENT}_1") (class "Default")
      (node (ref "R86") (pin "2") (pinfunction "2_2") (pintype "passive"))
    )
    (net (code "117") (name "/~{WIFI_CS}") (class "Default")
      (node (ref "R78") (pin "2") (pinfunction "2_2") (pintype "passive"))
    )
    (net (code "118") (name "/~{WIFI_CS}_1") (class "Default")
      (node (ref "R78") (pin "1") (pinfunction "1_1") (pintype "passive"))
    )
    (net (code "119") (name "/~{WIFI_HIBERNATE}") (class "Default")
      (node (ref "R80") (pin "2") (pinfunction "2_2") (pintype "passive"))
    )
    (net (code "120") (name "/~{WIFI_HIBERNATE}_1") (class "Default")
      (node (ref "R80") (pin "1") (pinfunction "1_1") (pintype "passive"))
    )
    (net (code "121") (name "/~{WIFI_ON}") (class "Default")
      (node (ref "R15") (pin "1") (pinfunction "1_1") (pintype "passive"))
      (node (ref "R16") (pin "2") (pinfunction "2_2") (pintype "passive"))
    )
    (net (code "122") (name "/~{WIFI_SPI_INT}") (class "Default")
      (node (ref "R81") (pin "2") (pinfunction "2_2") (pintype "passive"))
    )
    (net (code "123") (name "/~{WIFI_SPI_INT}_1") (class "Default")
      (node (ref "R81") (pin "1") (pinfunction "1_1") (pintype "passive"))
    )
    (net (code "124") (name "3.3V_Rail") (class "Default")
      (node (ref "BLE_Short") (pin "1") (pinfunction "A_1") (pintype "passive"))
      (node (ref "Bee_short") (pin "1") (pinfunction "A_1") (pintype "passive"))
      (node (ref "Ethernet_Short") (pin "1") (pinfunction "A_1") (pintype "passive"))
      (node (ref "F1") (pin "1") (pinfunction "1_1") (pintype "passive"))
      (node (ref "F2") (pin "1") (pinfunction "1_1") (pintype "passive"))
      (node (ref "F3") (pin "1") (pinfunction "1_1") (pintype "passive"))
      (node (ref "F4") (pin "1") (pinfunction "1_1") (pintype "passive"))
      (node (ref "F5") (pin "1") (pinfunction "1_1") (pintype "passive"))
      (node (ref "F6") (pin "1") (pinfunction "1_1") (pintype "passive"))
      (node (ref "F7") (pin "1") (pinfunction "1_1") (pintype "passive"))
      (node (ref "LoRa_short") (pin "1") (pinfunction "A_1") (pintype "passive"))
      (node (ref "Processor_short") (pin "1") (pinfunction "A_1") (pintype "passive"))
      (node (ref "Wifi_short") (pin "1") (pinfunction "A_1") (pintype "passive"))
      (node (ref "mem_sc") (pin "1") (pinfunction "A_1") (pintype "passive"))
    )
    (net (code "126") (name "Net-(BLE_Short-K)") (class "Default")
      (node (ref "BLE_Short") (pin "2") (pinfunction "K_2") (pintype "passive"))
      (node (ref "R110") (pin "1") (pinfunction "1_1") (pintype "passive"))
    )
    (net (code "127") (name "Net-(Bee_short-K)") (class "Default")
      (node (ref "Bee_short") (pin "2") (pinfunction "K_2") (pintype "passive"))
      (node (ref "R35") (pin "1") (pinfunction "1_1") (pintype "passive"))
    )
    (net (code "128") (name "Net-(Ethernet_Short-K)") (class "Default")
      (node (ref "Ethernet_Short") (pin "2") (pinfunction "K_2") (pintype "passive"))
      (node (ref "R131") (pin "1") (pinfunction "1_1") (pintype "passive"))
    )
    (net (code "129") (name "Net-(LoRa_short-K)") (class "Default")
      (node (ref "LoRa_short") (pin "2") (pinfunction "K_2") (pintype "passive"))
      (node (ref "R101") (pin "1") (pinfunction "1_1") (pintype "passive"))
    )
    (net (code "130") (name "Net-(Processor_short-K)") (class "Default")
      (node (ref "Processor_short") (pin "2") (pinfunction "K_2") (pintype "passive"))
      (node (ref "R151") (pin "1") (pinfunction "1_1") (pintype "passive"))
    )
    (net (code "131") (name "Net-(Q1-G)") (class "Default")
      (node (ref "C19") (pin "1") (pinfunction "1_1") (pintype "passive"))
      (node (ref "Q1") (pin "2") (pinfunction "G_2") (pintype "passive"))
      (node (ref "R16") (pin "1") (pinfunction "1_1") (pintype "passive"))
    )
    (net (code "132") (name "Net-(Q1-S)") (class "Default")
      (node (ref "F1") (pin "2") (pinfunction "2_2") (pintype "passive"))
      (node (ref "Q1") (pin "3") (pinfunction "S_3") (pintype "passive"))
      (node (ref "R15") (pin "2") (pinfunction "2_2") (pintype "passive"))
      (node (ref "R79") (pin "2") (pinfunction "2_2") (pintype "passive"))
    )
    (net (code "133") (name "Net-(Q2-G)") (class "Default")
      (node (ref "C20") (pin "1") (pinfunction "1_1") (pintype "passive"))
      (node (ref "Q2") (pin "2") (pinfunction "G_2") (pintype "passive"))
      (node (ref "R18") (pin "1") (pinfunction "1_1") (pintype "passive"))
    )
    (net (code "134") (name "Net-(Q2-S)") (class "Default")
      (node (ref "F2") (pin "2") (pinfunction "2_2") (pintype "passive"))
      (node (ref "Q2") (pin "3") (pinfunction "S_3") (pintype "passive"))
      (node (ref "R17") (pin "2") (pinfunction "2_2") (pintype "passive"))
      (node (ref "R88") (pin "2") (pinfunction "2_2") (pintype "passive"))
    )
    (net (code "135") (name "Net-(Q3-G)") (class "Default")
      (node (ref "C21") (pin "1") (pinfunction "1_1") (pintype "passive"))
      (node (ref "Q3") (pin "2") (pinfunction "G_2") (pintype "passive"))
      (node (ref "R20") (pin "1") (pinfunction "1_1") (pintype "passive"))
    )
    (net (code "136") (name "Net-(Q3-S)") (class "Default")
      (node (ref "F3") (pin "2") (pinfunction "2_2") (pintype "passive"))
      (node (ref "Q3") (pin "3") (pinfunction "S_3") (pintype "passive"))
      (node (ref "R101") (pin "2") (pinfunction "2_2") (pintype "passive"))
      (node (ref "R19") (pin "2") (pinfunction "2_2") (pintype "passive"))
    )
    (net (code "137") (name "Net-(Q4-G)") (class "Default")
      (node (ref "C22") (pin "1") (pinfunction "1_1") (pintype "passive"))
      (node (ref "Q4") (pin "2") (pinfunction "G_2") (pintype "passive"))
      (node (ref "R22") (pin "1") (pinfunction "1_1") (pintype "passive"))
    )
    (net (code "138") (name "Net-(Q4-S)") (class "Default")
      (node (ref "F4") (pin "2") (pinfunction "2_2") (pintype "passive"))
      (node (ref "Q4") (pin "3") (pinfunction "S_3") (pintype "passive"))
      (node (ref "R110") (pin "2") (pinfunction "2_2") (pintype "passive"))
      (node (ref "R21") (pin "2") (pinfunction "2_2") (pintype "passive"))
    )
    (net (code "139") (name "Net-(Q5-G)") (class "Default")
      (node (ref "C23") (pin "1") (pinfunction "1_1") (pintype "passive"))
      (node (ref "Q5") (pin "2") (pinfunction "G_2") (pintype "passive"))
      (node (ref "R24") (pin "1") (pinfunction "1_1") (pintype "passive"))
    )
    (net (code "140") (name "Net-(Q5-S)") (class "Default")
      (node (ref "F5") (pin "2") (pinfunction "2_2") (pintype "passive"))
      (node (ref "Q5") (pin "3") (pinfunction "S_3") (pintype "passive"))
      (node (ref "R131") (pin "2") (pinfunction "2_2") (pintype "passive"))
      (node (ref "R23") (pin "2") (pinfunction "2_2") (pintype "passive"))
    )
    (net (code "141") (name "Net-(Q6-G)") (class "Default")
      (node (ref "C32") (pin "1") (pinfunction "1_1") (pintype "passive"))
      (node (ref "Q6") (pin "2") (pinfunction "G_2") (pintype "passive"))
      (node (ref "R39") (pin "2") (pinfunction "2_2") (pintype "passive"))
    )
    (net (code "142") (name "Net-(Q6-S)") (class "Default")
      (node (ref "F7") (pin "2") (pinfunction "2_2") (pintype "passive"))
      (node (ref "Q6") (pin "3") (pinfunction "S_3") (pintype "passive"))
      (node (ref "R35") (pin "2") (pinfunction "2_2") (pintype "passive"))
      (node (ref "R36") (pin "2") (pinfunction "2_2") (pintype "passive"))
    )
    (net (code "143") (name "Net-(Wifi_short-K)") (class "Default")
      (node (ref "R79") (pin "1") (pinfunction "1_1") (pintype "passive"))
      (node (ref "Wifi_short") (pin "2") (pinfunction "K_2") (pintype "passive"))
    )
    (net (code "144") (name "Net-(mem_sc-K)") (class "Default")
      (node (ref "R88") (pin "1") (pinfunction "1_1") (pintype "passive"))
      (node (ref "mem_sc") (pin "2") (pinfunction "K_2") (pintype "passive"))
    )
  )
)
